# fpga_ddr3l.net
KiCad netlist of a schematic drawn in Altium Designer
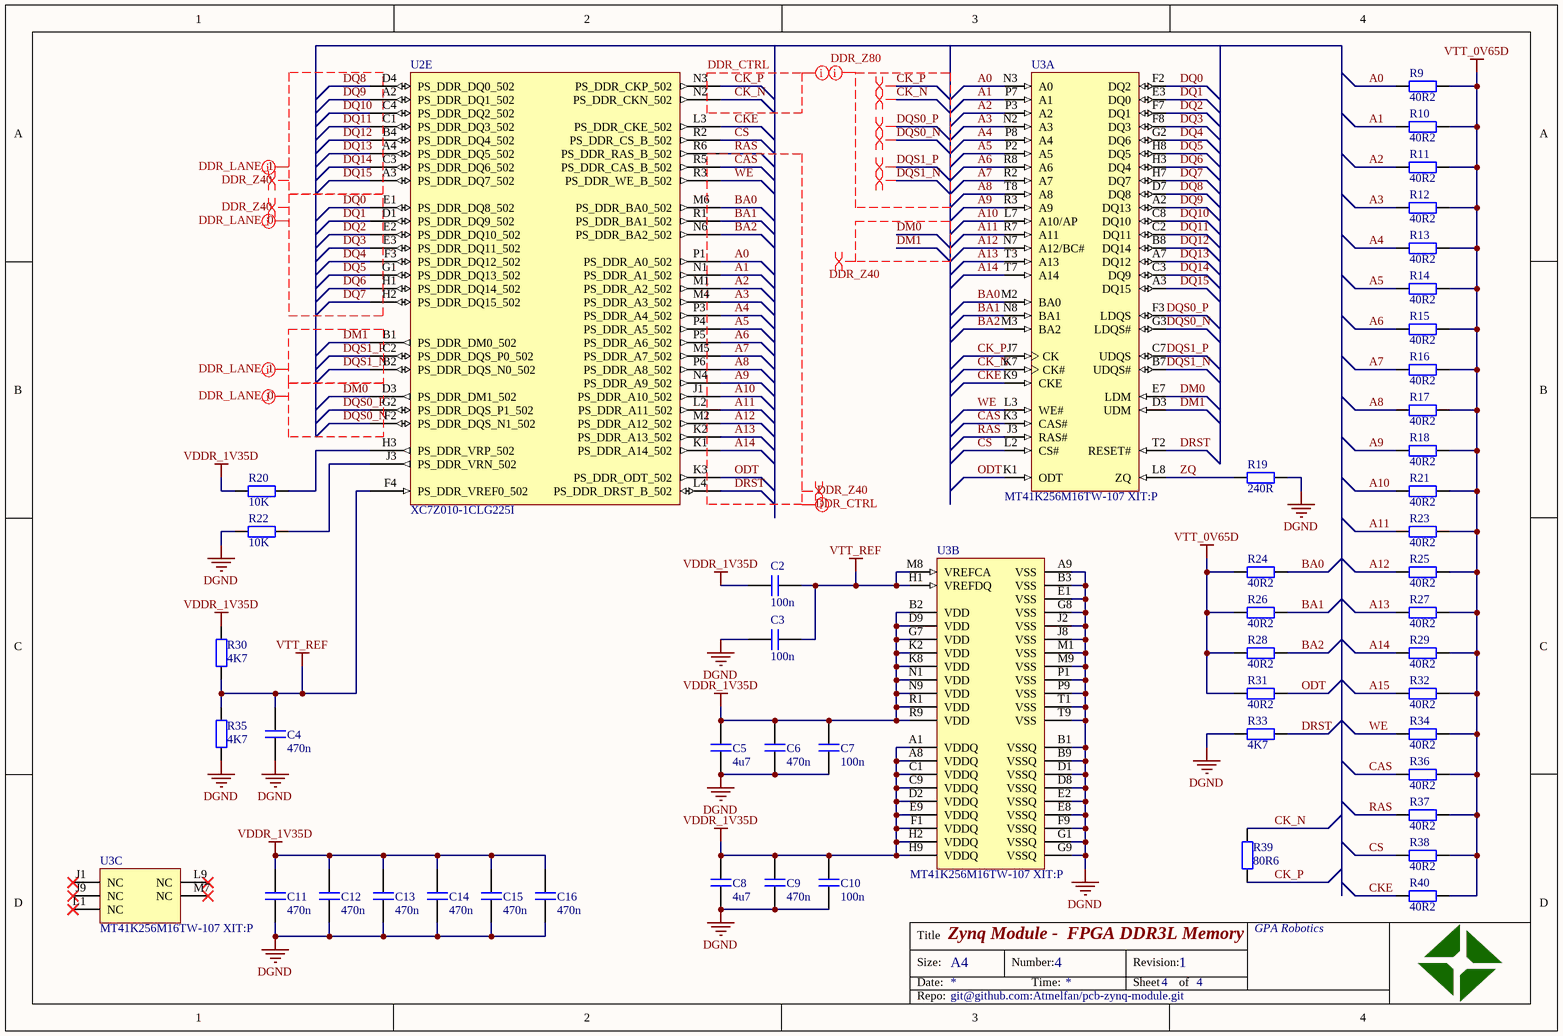
[diagram p0: fpga_ddr3l.SchDoc]

(export (version "E")
  (design (tool "Eeschema 10.0.6"))
  (components
    (comp (ref "C2")
      (value "100n")
      (footprint "CAPC1005X06N")
      (description "Capacitor")
      (fields (field (name "Comment") "cap"))
      (libsource (lib "lib_passives") (part "cap"))
    )
    (comp (ref "C3")
      (value "100n")
      (footprint "CAPC1005X06N")
      (description "Capacitor")
      (fields (field (name "Comment") "cap"))
      (libsource (lib "lib_passives") (part "cap"))
    )
    (comp (ref "C4")
      (value "470n")
      (footprint "CAPC1005X06N")
      (description "Capacitor")
      (fields (field (name "Comment") "cap"))
      (libsource (lib "lib_passives") (part "cap"))
    )
    (comp (ref "C5")
      (value "4u7")
      (footprint "CAPC1608X08N")
      (description "Capacitor")
      (fields (field (name "Comment") "cap"))
      (libsource (lib "lib_passives") (part "cap"))
    )
    (comp (ref "C6")
      (value "470n")
      (footprint "CAPC1005X06N")
      (description "Capacitor")
      (fields (field (name "Comment") "cap"))
      (libsource (lib "lib_passives") (part "cap"))
    )
    (comp (ref "C7")
      (value "100n")
      (footprint "CAPC1005X06N")
      (description "Capacitor")
      (fields (field (name "Comment") "cap"))
      (libsource (lib "lib_passives") (part "cap"))
    )
    (comp (ref "C8")
      (value "4u7")
      (footprint "CAPC1608X08N")
      (description "Capacitor")
      (fields (field (name "Comment") "cap"))
      (libsource (lib "lib_passives") (part "cap"))
    )
    (comp (ref "C9")
      (value "470n")
      (footprint "CAPC1005X06N")
      (description "Capacitor")
      (fields (field (name "Comment") "cap"))
      (libsource (lib "lib_passives") (part "cap"))
    )
    (comp (ref "C10")
      (value "100n")
      (footprint "CAPC1005X06N")
      (description "Capacitor")
      (fields (field (name "Comment") "cap"))
      (libsource (lib "lib_passives") (part "cap"))
    )
    (comp (ref "C11")
      (value "470n")
      (footprint "CAPC1005X06N")
      (description "Capacitor")
      (fields (field (name "Comment") "cap"))
      (libsource (lib "lib_passives") (part "cap"))
    )
    (comp (ref "C12")
      (value "470n")
      (footprint "CAPC1005X06N")
      (description "Capacitor")
      (fields (field (name "Comment") "cap"))
      (libsource (lib "lib_passives") (part "cap"))
    )
    (comp (ref "C13")
      (value "470n")
      (footprint "CAPC1005X06N")
      (description "Capacitor")
      (fields (field (name "Comment") "cap"))
      (libsource (lib "lib_passives") (part "cap"))
    )
    (comp (ref "C14")
      (value "470n")
      (footprint "CAPC1005X06N")
      (description "Capacitor")
      (fields (field (name "Comment") "cap"))
      (libsource (lib "lib_passives") (part "cap"))
    )
    (comp (ref "C15")
      (value "470n")
      (footprint "CAPC1005X06N")
      (description "Capacitor")
      (fields (field (name "Comment") "cap"))
      (libsource (lib "lib_passives") (part "cap"))
    )
    (comp (ref "C16")
      (value "470n")
      (footprint "CAPC1005X06N")
      (description "Capacitor")
      (fields (field (name "Comment") "cap"))
      (libsource (lib "lib_passives") (part "cap"))
    )
    (comp (ref "R9")
      (value "40R2")
      (footprint "RESC1005X04N")
      (description "Resistor")
      (fields (field (name "Comment") "res"))
      (libsource (lib "lib_passives") (part "res"))
    )
    (comp (ref "R10")
      (value "40R2")
      (footprint "RESC1005X04N")
      (description "Resistor")
      (fields (field (name "Comment") "res"))
      (libsource (lib "lib_passives") (part "res"))
    )
    (comp (ref "R11")
      (value "40R2")
      (footprint "RESC1005X04N")
      (description "Resistor")
      (fields (field (name "Comment") "res"))
      (libsource (lib "lib_passives") (part "res"))
    )
    (comp (ref "R12")
      (value "40R2")
      (footprint "RESC1005X04N")
      (description "Resistor")
      (fields (field (name "Comment") "res"))
      (libsource (lib "lib_passives") (part "res"))
    )
    (comp (ref "R13")
      (value "40R2")
      (footprint "RESC1005X04N")
      (description "Resistor")
      (fields (field (name "Comment") "res"))
      (libsource (lib "lib_passives") (part "res"))
    )
    (comp (ref "R14")
      (value "40R2")
      (footprint "RESC1005X04N")
      (description "Resistor")
      (fields (field (name "Comment") "res"))
      (libsource (lib "lib_passives") (part "res"))
    )
    (comp (ref "R15")
      (value "40R2")
      (footprint "RESC1005X04N")
      (description "Resistor")
      (fields (field (name "Comment") "res"))
      (libsource (lib "lib_passives") (part "res"))
    )
    (comp (ref "R16")
      (value "40R2")
      (footprint "RESC1005X04N")
      (description "Resistor")
      (fields (field (name "Comment") "res"))
      (libsource (lib "lib_passives") (part "res"))
    )
    (comp (ref "R17")
      (value "40R2")
      (footprint "RESC1005X04N")
      (description "Resistor")
      (fields (field (name "Comment") "res"))
      (libsource (lib "lib_passives") (part "res"))
    )
    (comp (ref "R18")
      (value "40R2")
      (footprint "RESC1005X04N")
      (description "Resistor")
      (fields (field (name "Comment") "res"))
      (libsource (lib "lib_passives") (part "res"))
    )
    (comp (ref "R19")
      (value "240R")
      (footprint "RESC1005X04N")
      (description "Resistor")
      (fields (field (name "Comment") "res"))
      (libsource (lib "lib_passives") (part "res"))
    )
    (comp (ref "R20")
      (value "10K")
      (footprint "RESC1005X04N")
      (description "Resistor")
      (fields (field (name "Comment") "res"))
      (libsource (lib "lib_passives") (part "res"))
    )
    (comp (ref "R21")
      (value "40R2")
      (footprint "RESC1005X04N")
      (description "Resistor")
      (fields (field (name "Comment") "res"))
      (libsource (lib "lib_passives") (part "res"))
    )
    (comp (ref "R22")
      (value "10K")
      (footprint "RESC1005X04N")
      (description "Resistor")
      (fields (field (name "Comment") "res"))
      (libsource (lib "lib_passives") (part "res"))
    )
    (comp (ref "R23")
      (value "40R2")
      (footprint "RESC1005X04N")
      (description "Resistor")
      (fields (field (name "Comment") "res"))
      (libsource (lib "lib_passives") (part "res"))
    )
    (comp (ref "R24")
      (value "40R2")
      (footprint "RESC1005X04N")
      (description "Resistor")
      (fields (field (name "Comment") "res"))
      (libsource (lib "") (part "res_2"))
    )
    (comp (ref "R25")
      (value "40R2")
      (footprint "RESC1005X04N")
      (description "Resistor")
      (fields (field (name "Comment") "res"))
      (libsource (lib "lib_passives") (part "res"))
    )
    (comp (ref "R26")
      (value "40R2")
      (footprint "RESC1005X04N")
      (description "Resistor")
      (fields (field (name "Comment") "res"))
      (libsource (lib "") (part "res_2"))
    )
    (comp (ref "R27")
      (value "40R2")
      (footprint "RESC1005X04N")
      (description "Resistor")
      (fields (field (name "Comment") "res"))
      (libsource (lib "lib_passives") (part "res"))
    )
    (comp (ref "R28")
      (value "40R2")
      (footprint "RESC1005X04N")
      (description "Resistor")
      (fields (field (name "Comment") "res"))
      (libsource (lib "") (part "res_2"))
    )
    (comp (ref "R29")
      (value "40R2")
      (footprint "RESC1005X04N")
      (description "Resistor")
      (fields (field (name "Comment") "res"))
      (libsource (lib "lib_passives") (part "res"))
    )
    (comp (ref "R30")
      (value "4K7")
      (footprint "RESC1005X04N")
      (description "Resistor")
      (fields (field (name "Comment") "res"))
      (libsource (lib "") (part "res_1"))
    )
    (comp (ref "R31")
      (value "40R2")
      (footprint "RESC1005X04N")
      (description "Resistor")
      (fields (field (name "Comment") "res"))
      (libsource (lib "") (part "res_2"))
    )
    (comp (ref "R32")
      (value "40R2")
      (footprint "RESC1005X04N")
      (description "Resistor")
      (fields (field (name "Comment") "res"))
      (libsource (lib "lib_passives") (part "res"))
    )
    (comp (ref "R33")
      (value "4K7")
      (footprint "RESC1005X04N")
      (description "Resistor")
      (fields (field (name "Comment") "res"))
      (libsource (lib "") (part "res_2"))
    )
    (comp (ref "R34")
      (value "40R2")
      (footprint "RESC1005X04N")
      (description "Resistor")
      (fields (field (name "Comment") "res"))
      (libsource (lib "lib_passives") (part "res"))
    )
    (comp (ref "R35")
      (value "4K7")
      (footprint "RESC1005X04N")
      (description "Resistor")
      (fields (field (name "Comment") "res"))
      (libsource (lib "") (part "res_1"))
    )
    (comp (ref "R36")
      (value "40R2")
      (footprint "RESC1005X04N")
      (description "Resistor")
      (fields (field (name "Comment") "res"))
      (libsource (lib "lib_passives") (part "res"))
    )
    (comp (ref "R37")
      (value "40R2")
      (footprint "RESC1005X04N")
      (description "Resistor")
      (fields (field (name "Comment") "res"))
      (libsource (lib "lib_passives") (part "res"))
    )
    (comp (ref "R38")
      (value "40R2")
      (footprint "RESC1005X04N")
      (description "Resistor")
      (fields (field (name "Comment") "res"))
      (libsource (lib "lib_passives") (part "res"))
    )
    (comp (ref "R39")
      (value "80R6")
      (footprint "RESC1005X04N")
      (description "Resistor")
      (fields (field (name "Comment") "res"))
      (libsource (lib "") (part "res_3"))
    )
    (comp (ref "R40")
      (value "40R2")
      (footprint "RESC1005X04N")
      (description "Resistor")
      (fields (field (name "Comment") "res"))
      (libsource (lib "lib_passives") (part "res"))
    )
    (comp (ref "U2")
      (value "XC7Z010-1CLG225I")
      (footprint "CLG225")
      (fields (field (name "GENERIC PART NUMBER") "XC7Z010"))
      (libsource (lib "Altium Content Vault") (part "XNLX-XC7Z010-CLG225"))
    )
    (comp (ref "U3")
      (value "MT41K256M16TW-107 XIT:P")
      (footprint "MICT-TW-96")
      (description "DDR3L SDRAM, 4 GB, 933 MHz, 1.283 to 1.45 V, -40 to 95 degC, 96-Pin FBGA, RoHs, Tray")
      (fields (field (name "MANUFACTURER") "Micron"))
      (libsource (lib "") (part "MICT-MT41K256M16-TW-96_1"))
    )
  )
  (nets
    (net (code "1") (name "/A0") (class "Default")
      (node (ref "R9") (pin "1") (pinfunction "1_1") (pintype "passive"))
      (node (ref "U2") (pin "P1") (pinfunction "PS_DDR_A0_502_P1") (pintype "output"))
      (node (ref "U3") (pin "N3") (pinfunction "A0_N3") (pintype "input"))
    )
    (net (code "2") (name "/A1") (class "Default")
      (node (ref "R10") (pin "1") (pinfunction "1_1") (pintype "passive"))
      (node (ref "U2") (pin "N1") (pinfunction "PS_DDR_A1_502_N1") (pintype "output"))
      (node (ref "U3") (pin "P7") (pinfunction "A1_P7") (pintype "input"))
    )
    (net (code "3") (name "/A2") (class "Default")
      (node (ref "R11") (pin "1") (pinfunction "1_1") (pintype "passive"))
      (node (ref "U2") (pin "M1") (pinfunction "PS_DDR_A2_502_M1") (pintype "output"))
      (node (ref "U3") (pin "P3") (pinfunction "A2_P3") (pintype "input"))
    )
    (net (code "4") (name "/A3") (class "Default")
      (node (ref "R12") (pin "1") (pinfunction "1_1") (pintype "passive"))
      (node (ref "U2") (pin "M4") (pinfunction "PS_DDR_A3_502_M4") (pintype "output"))
      (node (ref "U3") (pin "N2") (pinfunction "A3_N2") (pintype "input"))
    )
    (net (code "5") (name "/A4") (class "Default")
      (node (ref "R13") (pin "1") (pinfunction "1_1") (pintype "passive"))
      (node (ref "U2") (pin "P3") (pinfunction "PS_DDR_A4_502_P3") (pintype "output"))
      (node (ref "U3") (pin "P8") (pinfunction "A4_P8") (pintype "input"))
    )
    (net (code "6") (name "/A5") (class "Default")
      (node (ref "R14") (pin "1") (pinfunction "1_1") (pintype "passive"))
      (node (ref "U2") (pin "P4") (pinfunction "PS_DDR_A5_502_P4") (pintype "output"))
      (node (ref "U3") (pin "P2") (pinfunction "A5_P2") (pintype "input"))
    )
    (net (code "7") (name "/A6") (class "Default")
      (node (ref "R15") (pin "1") (pinfunction "1_1") (pintype "passive"))
      (node (ref "U2") (pin "P5") (pinfunction "PS_DDR_A6_502_P5") (pintype "output"))
      (node (ref "U3") (pin "R8") (pinfunction "A6_R8") (pintype "input"))
    )
    (net (code "8") (name "/A7") (class "Default")
      (node (ref "R16") (pin "1") (pinfunction "1_1") (pintype "passive"))
      (node (ref "U2") (pin "M5") (pinfunction "PS_DDR_A7_502_M5") (pintype "output"))
      (node (ref "U3") (pin "R2") (pinfunction "A7_R2") (pintype "input"))
    )
    (net (code "9") (name "/A8") (class "Default")
      (node (ref "R17") (pin "1") (pinfunction "1_1") (pintype "passive"))
      (node (ref "U2") (pin "P6") (pinfunction "PS_DDR_A8_502_P6") (pintype "output"))
      (node (ref "U3") (pin "T8") (pinfunction "A8_T8") (pintype "input"))
    )
    (net (code "10") (name "/A9") (class "Default")
      (node (ref "R18") (pin "1") (pinfunction "1_1") (pintype "passive"))
      (node (ref "U2") (pin "N4") (pinfunction "PS_DDR_A9_502_N4") (pintype "output"))
      (node (ref "U3") (pin "R3") (pinfunction "A9_R3") (pintype "input"))
    )
    (net (code "11") (name "/A10") (class "Default")
      (node (ref "R21") (pin "1") (pinfunction "1_1") (pintype "passive"))
      (node (ref "U2") (pin "J1") (pinfunction "PS_DDR_A10_502_J1") (pintype "output"))
      (node (ref "U3") (pin "L7") (pinfunction "A10/AP_L7") (pintype "input"))
    )
    (net (code "12") (name "/A11") (class "Default")
      (node (ref "R23") (pin "1") (pinfunction "1_1") (pintype "passive"))
      (node (ref "U2") (pin "L2") (pinfunction "PS_DDR_A11_502_L2") (pintype "output"))
      (node (ref "U3") (pin "R7") (pinfunction "A11_R7") (pintype "input"))
    )
    (net (code "13") (name "/A12") (class "Default")
      (node (ref "R25") (pin "1") (pinfunction "1_1") (pintype "passive"))
      (node (ref "U2") (pin "M2") (pinfunction "PS_DDR_A12_502_M2") (pintype "output"))
      (node (ref "U3") (pin "N7") (pinfunction "A12/BC#_N7") (pintype "input"))
    )
    (net (code "14") (name "/A13") (class "Default")
      (node (ref "R27") (pin "1") (pinfunction "1_1") (pintype "passive"))
      (node (ref "U2") (pin "K2") (pinfunction "PS_DDR_A13_502_K2") (pintype "output"))
      (node (ref "U3") (pin "T3") (pinfunction "A13_T3") (pintype "input"))
    )
    (net (code "15") (name "/A14") (class "Default")
      (node (ref "R29") (pin "1") (pinfunction "1_1") (pintype "passive"))
      (node (ref "U2") (pin "K1") (pinfunction "PS_DDR_A14_502_K1") (pintype "output"))
      (node (ref "U3") (pin "T7") (pinfunction "A14_T7") (pintype "input"))
    )
    (net (code "16") (name "/A15") (class "Default")
      (node (ref "R32") (pin "1") (pinfunction "1_1") (pintype "passive"))
    )
    (net (code "17") (name "/BA0") (class "Default")
      (node (ref "R24") (pin "1") (pinfunction "1_1") (pintype "passive"))
      (node (ref "U2") (pin "M6") (pinfunction "PS_DDR_BA0_502_M6") (pintype "output"))
      (node (ref "U3") (pin "M2") (pinfunction "BA0_M2") (pintype "input"))
    )
    (net (code "18") (name "/BA1") (class "Default")
      (node (ref "R26") (pin "1") (pinfunction "1_1") (pintype "passive"))
      (node (ref "U2") (pin "R1") (pinfunction "PS_DDR_BA1_502_R1") (pintype "output"))
      (node (ref "U3") (pin "N8") (pinfunction "BA1_N8") (pintype "input"))
    )
    (net (code "19") (name "/BA2") (class "Default")
      (node (ref "R28") (pin "1") (pinfunction "1_1") (pintype "passive"))
      (node (ref "U2") (pin "N6") (pinfunction "PS_DDR_BA2_502_N6") (pintype "output"))
      (node (ref "U3") (pin "M3") (pinfunction "BA2_M3") (pintype "input"))
    )
    (net (code "20") (name "/CAS") (class "Default")
      (node (ref "R36") (pin "1") (pinfunction "1_1") (pintype "passive"))
      (node (ref "U2") (pin "R5") (pinfunction "PS_DDR_CAS_B_502_R5") (pintype "output"))
      (node (ref "U3") (pin "K3") (pinfunction "CAS#_K3") (pintype "input"))
    )
    (net (code "21") (name "/CKE") (class "Default")
      (node (ref "R40") (pin "1") (pinfunction "1_1") (pintype "passive"))
      (node (ref "U2") (pin "L3") (pinfunction "PS_DDR_CKE_502_L3") (pintype "output"))
      (node (ref "U3") (pin "K9") (pinfunction "CKE_K9") (pintype "input"))
    )
    (net (code "22") (name "/CK_N") (class "Default")
      (node (ref "R39") (pin "1") (pinfunction "1_1") (pintype "passive"))
      (node (ref "U2") (pin "N2") (pinfunction "PS_DDR_CKN_502_N2") (pintype "output"))
      (node (ref "U3") (pin "K7") (pinfunction "CK#_K7") (pintype "input"))
    )
    (net (code "23") (name "/CK_P") (class "Default")
      (node (ref "R39") (pin "2") (pinfunction "2_2") (pintype "passive"))
      (node (ref "U2") (pin "N3") (pinfunction "PS_DDR_CKP_502_N3") (pintype "output"))
      (node (ref "U3") (pin "J7") (pinfunction "CK_J7") (pintype "input"))
    )
    (net (code "24") (name "/CS") (class "Default")
      (node (ref "R38") (pin "1") (pinfunction "1_1") (pintype "passive"))
      (node (ref "U2") (pin "R2") (pinfunction "PS_DDR_CS_B_502_R2") (pintype "output"))
      (node (ref "U3") (pin "L2") (pinfunction "CS#_L2") (pintype "input"))
    )
    (net (code "25") (name "/DM0") (class "Default")
      (node (ref "U2") (pin "D3") (pinfunction "PS_DDR_DM1_502_D3") (pintype "output"))
      (node (ref "U3") (pin "E7") (pinfunction "LDM_E7") (pintype "input"))
    )
    (net (code "26") (name "/DM1") (class "Default")
      (node (ref "U2") (pin "B1") (pinfunction "PS_DDR_DM0_502_B1") (pintype "output"))
      (node (ref "U3") (pin "D3") (pinfunction "UDM_D3") (pintype "input"))
    )
    (net (code "27") (name "/DQ0") (class "Default")
      (node (ref "U2") (pin "E1") (pinfunction "PS_DDR_DQ8_502_E1") (pintype "bidirectional"))
      (node (ref "U3") (pin "F2") (pinfunction "DQ2_F2") (pintype "bidirectional"))
    )
    (net (code "28") (name "/DQ1") (class "Default")
      (node (ref "U2") (pin "D1") (pinfunction "PS_DDR_DQ9_502_D1") (pintype "bidirectional"))
      (node (ref "U3") (pin "E3") (pinfunction "DQ0_E3") (pintype "bidirectional"))
    )
    (net (code "29") (name "/DQ2") (class "Default")
      (node (ref "U2") (pin "E2") (pinfunction "PS_DDR_DQ10_502_E2") (pintype "bidirectional"))
      (node (ref "U3") (pin "F7") (pinfunction "DQ1_F7") (pintype "bidirectional"))
    )
    (net (code "30") (name "/DQ3") (class "Default")
      (node (ref "U2") (pin "E3") (pinfunction "PS_DDR_DQ11_502_E3") (pintype "bidirectional"))
      (node (ref "U3") (pin "F8") (pinfunction "DQ3_F8") (pintype "bidirectional"))
    )
    (net (code "31") (name "/DQ4") (class "Default")
      (node (ref "U2") (pin "F3") (pinfunction "PS_DDR_DQ12_502_F3") (pintype "bidirectional"))
      (node (ref "U3") (pin "G2") (pinfunction "DQ6_G2") (pintype "bidirectional"))
    )
    (net (code "32") (name "/DQ5") (class "Default")
      (node (ref "U2") (pin "G1") (pinfunction "PS_DDR_DQ13_502_G1") (pintype "bidirectional"))
      (node (ref "U3") (pin "H8") (pinfunction "DQ5_H8") (pintype "bidirectional"))
    )
    (net (code "33") (name "/DQ6") (class "Default")
      (node (ref "U2") (pin "H1") (pinfunction "PS_DDR_DQ14_502_H1") (pintype "bidirectional"))
      (node (ref "U3") (pin "H3") (pinfunction "DQ4_H3") (pintype "bidirectional"))
    )
    (net (code "34") (name "/DQ7") (class "Default")
      (node (ref "U2") (pin "H2") (pinfunction "PS_DDR_DQ15_502_H2") (pintype "bidirectional"))
      (node (ref "U3") (pin "H7") (pinfunction "DQ7_H7") (pintype "bidirectional"))
    )
    (net (code "35") (name "/DQ8") (class "Default")
      (node (ref "U2") (pin "D4") (pinfunction "PS_DDR_DQ0_502_D4") (pintype "bidirectional"))
      (node (ref "U3") (pin "D7") (pinfunction "DQ8_D7") (pintype "bidirectional"))
    )
    (net (code "36") (name "/DQ9") (class "Default")
      (node (ref "U2") (pin "A2") (pinfunction "PS_DDR_DQ1_502_A2") (pintype "bidirectional"))
      (node (ref "U3") (pin "A2") (pinfunction "DQ13_A2") (pintype "bidirectional"))
    )
    (net (code "37") (name "/DQ10") (class "Default")
      (node (ref "U2") (pin "C4") (pinfunction "PS_DDR_DQ2_502_C4") (pintype "bidirectional"))
      (node (ref "U3") (pin "C8") (pinfunction "DQ10_C8") (pintype "bidirectional"))
    )
    (net (code "38") (name "/DQ11") (class "Default")
      (node (ref "U2") (pin "C1") (pinfunction "PS_DDR_DQ3_502_C1") (pintype "bidirectional"))
      (node (ref "U3") (pin "C2") (pinfunction "DQ11_C2") (pintype "bidirectional"))
    )
    (net (code "39") (name "/DQ12") (class "Default")
      (node (ref "U2") (pin "B4") (pinfunction "PS_DDR_DQ4_502_B4") (pintype "bidirectional"))
      (node (ref "U3") (pin "B8") (pinfunction "DQ14_B8") (pintype "bidirectional"))
    )
    (net (code "40") (name "/DQ13") (class "Default")
      (node (ref "U2") (pin "A4") (pinfunction "PS_DDR_DQ5_502_A4") (pintype "bidirectional"))
      (node (ref "U3") (pin "A7") (pinfunction "DQ12_A7") (pintype "bidirectional"))
    )
    (net (code "41") (name "/DQ14") (class "Default")
      (node (ref "U2") (pin "C3") (pinfunction "PS_DDR_DQ6_502_C3") (pintype "bidirectional"))
      (node (ref "U3") (pin "C3") (pinfunction "DQ9_C3") (pintype "bidirectional"))
    )
    (net (code "42") (name "/DQ15") (class "Default")
      (node (ref "U2") (pin "A3") (pinfunction "PS_DDR_DQ7_502_A3") (pintype "bidirectional"))
      (node (ref "U3") (pin "A3") (pinfunction "DQ15_A3") (pintype "bidirectional"))
    )
    (net (code "43") (name "/DQS0_N") (class "Default")
      (node (ref "U2") (pin "F2") (pinfunction "PS_DDR_DQS_N1_502_F2") (pintype "bidirectional"))
      (node (ref "U3") (pin "G3") (pinfunction "LDQS#_G3") (pintype "bidirectional"))
    )
    (net (code "44") (name "/DQS0_P") (class "Default")
      (node (ref "U2") (pin "G2") (pinfunction "PS_DDR_DQS_P1_502_G2") (pintype "bidirectional"))
      (node (ref "U3") (pin "F3") (pinfunction "LDQS_F3") (pintype "bidirectional"))
    )
    (net (code "45") (name "/DQS1_N") (class "Default")
      (node (ref "U2") (pin "B2") (pinfunction "PS_DDR_DQS_N0_502_B2") (pintype "bidirectional"))
      (node (ref "U3") (pin "B7") (pinfunction "UDQS#_B7") (pintype "bidirectional"))
    )
    (net (code "46") (name "/DQS1_P") (class "Default")
      (node (ref "U2") (pin "C2") (pinfunction "PS_DDR_DQS_P0_502_C2") (pintype "bidirectional"))
      (node (ref "U3") (pin "C7") (pinfunction "UDQS_C7") (pintype "bidirectional"))
    )
    (net (code "47") (name "/DRST") (class "Default")
      (node (ref "R33") (pin "1") (pinfunction "1_1") (pintype "passive"))
      (node (ref "U2") (pin "L4") (pinfunction "PS_DDR_DRST_B_502_L4") (pintype "bidirectional"))
      (node (ref "U3") (pin "T2") (pinfunction "RESET#_T2") (pintype "input"))
    )
    (net (code "48") (name "/ODT") (class "Default")
      (node (ref "R31") (pin "1") (pinfunction "1_1") (pintype "passive"))
      (node (ref "U2") (pin "K3") (pinfunction "PS_DDR_ODT_502_K3") (pintype "output"))
      (node (ref "U3") (pin "K1") (pinfunction "ODT_K1") (pintype "input"))
    )
    (net (code "49") (name "/RAS") (class "Default")
      (node (ref "R37") (pin "1") (pinfunction "1_1") (pintype "passive"))
      (node (ref "U2") (pin "R6") (pinfunction "PS_DDR_RAS_B_502_R6") (pintype "output"))
      (node (ref "U3") (pin "J3") (pinfunction "RAS#_J3") (pintype "input"))
    )
    (net (code "50") (name "/WE") (class "Default")
      (node (ref "R34") (pin "1") (pinfunction "1_1") (pintype "passive"))
      (node (ref "U2") (pin "R3") (pinfunction "PS_DDR_WE_B_502_R3") (pintype "output"))
      (node (ref "U3") (pin "L3") (pinfunction "WE#_L3") (pintype "input"))
    )
    (net (code "51") (name "/ZQ") (class "Default")
      (node (ref "R19") (pin "1") (pinfunction "1_1") (pintype "passive"))
      (node (ref "U3") (pin "L8") (pinfunction "ZQ_L8") (pintype "input"))
    )
    (net (code "52") (name "DGND") (class "Default")
      (node (ref "C10") (pin "1") (pinfunction "1_1") (pintype "passive"))
      (node (ref "C11") (pin "1") (pinfunction "1_1") (pintype "passive"))
      (node (ref "C12") (pin "1") (pinfunction "1_1") (pintype "passive"))
      (node (ref "C13") (pin "1") (pinfunction "1_1") (pintype "passive"))
      (node (ref "C14") (pin "1") (pinfunction "1_1") (pintype "passive"))
      (node (ref "C15") (pin "1") (pinfunction "1_1") (pintype "passive"))
      (node (ref "C16") (pin "1") (pinfunction "1_1") (pintype "passive"))
      (node (ref "C3") (pin "1") (pinfunction "1_1") (pintype "passive"))
      (node (ref "C4") (pin "1") (pinfunction "1_1") (pintype "passive"))
      (node (ref "C5") (pin "1") (pinfunction "1_1") (pintype "passive"))
      (node (ref "C6") (pin "1") (pinfunction "1_1") (pintype "passive"))
      (node (ref "C7") (pin "1") (pinfunction "1_1") (pintype "passive"))
      (node (ref "C8") (pin "1") (pinfunction "1_1") (pintype "passive"))
      (node (ref "C9") (pin "1") (pinfunction "1_1") (pintype "passive"))
      (node (ref "R19") (pin "2") (pinfunction "2_2") (pintype "passive"))
      (node (ref "R22") (pin "1") (pinfunction "1_1") (pintype "passive"))
      (node (ref "R33") (pin "2") (pinfunction "2_2") (pintype "passive"))
      (node (ref "R35") (pin "1") (pinfunction "1_1") (pintype "passive"))
      (node (ref "U3") (pin "A9") (pinfunction "VSS_A9") (pintype "power_in"))
      (node (ref "U3") (pin "B1") (pinfunction "VSSQ_B1") (pintype "power_in"))
      (node (ref "U3") (pin "B3") (pinfunction "VSS_B3") (pintype "power_in"))
      (node (ref "U3") (pin "B9") (pinfunction "VSSQ_B9") (pintype "power_in"))
      (node (ref "U3") (pin "D1") (pinfunction "VSSQ_D1") (pintype "power_in"))
      (node (ref "U3") (pin "D8") (pinfunction "VSSQ_D8") (pintype "power_in"))
      (node (ref "U3") (pin "E1") (pinfunction "VSS_E1") (pintype "power_in"))
      (node (ref "U3") (pin "E2") (pinfunction "VSSQ_E2") (pintype "power_in"))
      (node (ref "U3") (pin "E8") (pinfunction "VSSQ_E8") (pintype "power_in"))
      (node (ref "U3") (pin "F9") (pinfunction "VSSQ_F9") (pintype "power_in"))
      (node (ref "U3") (pin "G1") (pinfunction "VSSQ_G1") (pintype "power_in"))
      (node (ref "U3") (pin "G8") (pinfunction "VSS_G8") (pintype "power_in"))
      (node (ref "U3") (pin "G9") (pinfunction "VSSQ_G9") (pintype "power_in"))
      (node (ref "U3") (pin "J2") (pinfunction "VSS_J2") (pintype "power_in"))
      (node (ref "U3") (pin "J8") (pinfunction "VSS_J8") (pintype "power_in"))
      (node (ref "U3") (pin "M1") (pinfunction "VSS_M1") (pintype "power_in"))
      (node (ref "U3") (pin "M9") (pinfunction "VSS_M9") (pintype "power_in"))
      (node (ref "U3") (pin "P1") (pinfunction "VSS_P1") (pintype "power_in"))
      (node (ref "U3") (pin "P9") (pinfunction "VSS_P9") (pintype "power_in"))
      (node (ref "U3") (pin "T1") (pinfunction "VSS_T1") (pintype "power_in"))
      (node (ref "U3") (pin "T9") (pinfunction "VSS_T9") (pintype "power_in"))
    )
    (net (code "53") (name "Net-(U2E-PS_DDR_VRN_502)") (class "Default")
      (node (ref "R22") (pin "2") (pinfunction "2_2") (pintype "passive"))
      (node (ref "U2") (pin "J3") (pinfunction "PS_DDR_VRN_502_J3") (pintype "output"))
    )
    (net (code "54") (name "Net-(U2E-PS_DDR_VRP_502)") (class "Default")
      (node (ref "R20") (pin "2") (pinfunction "2_2") (pintype "passive"))
      (node (ref "U2") (pin "H3") (pinfunction "PS_DDR_VRP_502_H3") (pintype "output"))
    )
    (net (code "55") (name "VDDR_1V35D") (class "Default")
      (node (ref "C10") (pin "2") (pinfunction "2_2") (pintype "passive"))
      (node (ref "C11") (pin "2") (pinfunction "2_2") (pintype "passive"))
      (node (ref "C12") (pin "2") (pinfunction "2_2") (pintype "passive"))
      (node (ref "C13") (pin "2") (pinfunction "2_2") (pintype "passive"))
      (node (ref "C14") (pin "2") (pinfunction "2_2") (pintype "passive"))
      (node (ref "C15") (pin "2") (pinfunction "2_2") (pintype "passive"))
      (node (ref "C16") (pin "2") (pinfunction "2_2") (pintype "passive"))
      (node (ref "C2") (pin "1") (pinfunction "1_1") (pintype "passive"))
      (node (ref "C5") (pin "2") (pinfunction "2_2") (pintype "passive"))
      (node (ref "C6") (pin "2") (pinfunction "2_2") (pintype "passive"))
      (node (ref "C7") (pin "2") (pinfunction "2_2") (pintype "passive"))
      (node (ref "C8") (pin "2") (pinfunction "2_2") (pintype "passive"))
      (node (ref "C9") (pin "2") (pinfunction "2_2") (pintype "passive"))
      (node (ref "R20") (pin "1") (pinfunction "1_1") (pintype "passive"))
      (node (ref "R30") (pin "2") (pinfunction "2_2") (pintype "passive"))
      (node (ref "U3") (pin "A1") (pinfunction "VDDQ_A1") (pintype "power_in"))
      (node (ref "U3") (pin "A8") (pinfunction "VDDQ_A8") (pintype "power_in"))
      (node (ref "U3") (pin "B2") (pinfunction "VDD_B2") (pintype "power_in"))
      (node (ref "U3") (pin "C1") (pinfunction "VDDQ_C1") (pintype "power_in"))
      (node (ref "U3") (pin "C9") (pinfunction "VDDQ_C9") (pintype "power_in"))
      (node (ref "U3") (pin "D2") (pinfunction "VDDQ_D2") (pintype "power_in"))
      (node (ref "U3") (pin "D9") (pinfunction "VDD_D9") (pintype "power_in"))
      (node (ref "U3") (pin "E9") (pinfunction "VDDQ_E9") (pintype "power_in"))
      (node (ref "U3") (pin "F1") (pinfunction "VDDQ_F1") (pintype "power_in"))
      (node (ref "U3") (pin "G7") (pinfunction "VDD_G7") (pintype "power_in"))
      (node (ref "U3") (pin "H2") (pinfunction "VDDQ_H2") (pintype "power_in"))
      (node (ref "U3") (pin "H9") (pinfunction "VDDQ_H9") (pintype "power_in"))
      (node (ref "U3") (pin "K2") (pinfunction "VDD_K2") (pintype "power_in"))
      (node (ref "U3") (pin "K8") (pinfunction "VDD_K8") (pintype "power_in"))
      (node (ref "U3") (pin "N1") (pinfunction "VDD_N1") (pintype "power_in"))
      (node (ref "U3") (pin "N9") (pinfunction "VDD_N9") (pintype "power_in"))
      (node (ref "U3") (pin "R1") (pinfunction "VDD_R1") (pintype "power_in"))
      (node (ref "U3") (pin "R9") (pinfunction "VDD_R9") (pintype "power_in"))
    )
    (net (code "56") (name "VTT_0V65D") (class "Default")
      (node (ref "R10") (pin "2") (pinfunction "2_2") (pintype "passive"))
      (node (ref "R11") (pin "2") (pinfunction "2_2") (pintype "passive"))
      (node (ref "R12") (pin "2") (pinfunction "2_2") (pintype "passive"))
      (node (ref "R13") (pin "2") (pinfunction "2_2") (pintype "passive"))
      (node (ref "R14") (pin "2") (pinfunction "2_2") (pintype "passive"))
      (node (ref "R15") (pin "2") (pinfunction "2_2") (pintype "passive"))
      (node (ref "R16") (pin "2") (pinfunction "2_2") (pintype "passive"))
      (node (ref "R17") (pin "2") (pinfunction "2_2") (pintype "passive"))
      (node (ref "R18") (pin "2") (pinfunction "2_2") (pintype "passive"))
      (node (ref "R21") (pin "2") (pinfunction "2_2") (pintype "passive"))
      (node (ref "R23") (pin "2") (pinfunction "2_2") (pintype "passive"))
      (node (ref "R24") (pin "2") (pinfunction "2_2") (pintype "passive"))
      (node (ref "R25") (pin "2") (pinfunction "2_2") (pintype "passive"))
      (node (ref "R26") (pin "2") (pinfunction "2_2") (pintype "passive"))
      (node (ref "R27") (pin "2") (pinfunction "2_2") (pintype "passive"))
      (node (ref "R28") (pin "2") (pinfunction "2_2") (pintype "passive"))
      (node (ref "R29") (pin "2") (pinfunction "2_2") (pintype "passive"))
      (node (ref "R31") (pin "2") (pinfunction "2_2") (pintype "passive"))
      (node (ref "R32") (pin "2") (pinfunction "2_2") (pintype "passive"))
      (node (ref "R34") (pin "2") (pinfunction "2_2") (pintype "passive"))
      (node (ref "R36") (pin "2") (pinfunction "2_2") (pintype "passive"))
      (node (ref "R37") (pin "2") (pinfunction "2_2") (pintype "passive"))
      (node (ref "R38") (pin "2") (pinfunction "2_2") (pintype "passive"))
      (node (ref "R40") (pin "2") (pinfunction "2_2") (pintype "passive"))
      (node (ref "R9") (pin "2") (pinfunction "2_2") (pintype "passive"))
    )
    (net (code "57") (name "VTT_REF") (class "Default")
      (node (ref "C2") (pin "2") (pinfunction "2_2") (pintype "passive"))
      (node (ref "C3") (pin "2") (pinfunction "2_2") (pintype "passive"))
      (node (ref "C4") (pin "2") (pinfunction "2_2") (pintype "passive"))
      (node (ref "R30") (pin "1") (pinfunction "1_1") (pintype "passive"))
      (node (ref "R35") (pin "2") (pinfunction "2_2") (pintype "passive"))
      (node (ref "U2") (pin "F4") (pinfunction "PS_DDR_VREF0_502_F4") (pintype "input"))
      (node (ref "U3") (pin "H1") (pinfunction "VREFDQ_H1") (pintype "input"))
      (node (ref "U3") (pin "M8") (pinfunction "VREFCA_M8") (pintype "input"))
    )
    (net (code "58") (name "unconnected-(U3C-NC-PadJ1)") (class "Default")
      (node (ref "U3") (pin "J1") (pinfunction "NC_J1") (pintype "passive+no_connect"))
    )
    (net (code "59") (name "unconnected-(U3C-NC-PadJ9)") (class "Default")
      (node (ref "U3") (pin "J9") (pinfunction "NC_J9") (pintype "passive+no_connect"))
    )
    (net (code "60") (name "unconnected-(U3C-NC-PadL1)") (class "Default")
      (node (ref "U3") (pin "L1") (pinfunction "NC_L1") (pintype "passive+no_connect"))
    )
    (net (code "61") (name "unconnected-(U3C-NC-PadL9)") (class "Default")
      (node (ref "U3") (pin "L9") (pinfunction "NC_L9") (pintype "passive+no_connect"))
    )
    (net (code "62") (name "unconnected-(U3C-NC-PadM7)") (class "Default")
      (node (ref "U3") (pin "M7") (pinfunction "NC_M7") (pintype "passive+no_connect"))
    )
  )
)
